# expansion.net
KiCad netlist of a schematic drawn in EAGLE
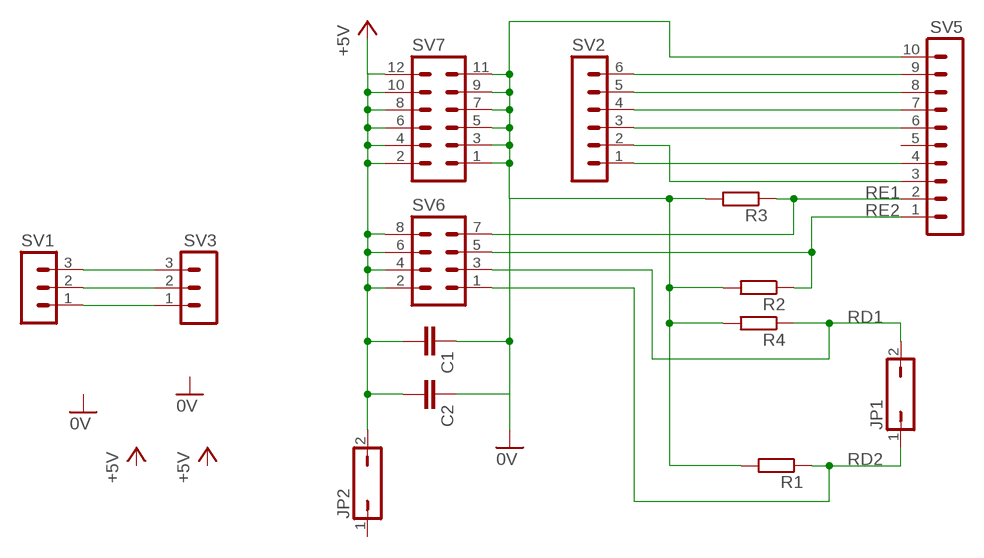
[diagram p0: schematic, sheet 1]

(export (version "E")
  (design (tool "Eeschema 10.0.6"))
  (components
    (comp (ref "C1")
      (value "C-EU025-030X050")
      (footprint "eagle-import:C025-030X050")
      (libsource (lib "eagle-import") (part "C-EU025-030X050"))
    )
    (comp (ref "C2")
      (value "C-EU025-030X050")
      (footprint "eagle-import:C025-030X050")
      (libsource (lib "eagle-import") (part "C-EU025-030X050"))
    )
    (comp (ref "JP1")
      (value "JP1Q")
      (footprint "eagle-import:JP1")
      (libsource (lib "eagle-import") (part "JP1Q"))
    )
    (comp (ref "JP2")
      (value "JP1Q")
      (footprint "eagle-import:JP1")
      (libsource (lib "eagle-import") (part "JP1Q"))
    )
    (comp (ref "R1")
      (value "R-EU_0207/10")
      (footprint "eagle-import:0207_10")
      (libsource (lib "eagle-import") (part "R-EU_0207/10"))
    )
    (comp (ref "R2")
      (value "R-EU_0207/5V")
      (footprint "eagle-import:0207_5V")
      (libsource (lib "eagle-import") (part "R-EU_0207/5V"))
    )
    (comp (ref "R3")
      (value "R-EU_0207/2V")
      (footprint "eagle-import:0207_2V")
      (libsource (lib "eagle-import") (part "R-EU_0207/2V"))
    )
    (comp (ref "R4")
      (value "R-EU_0204/7")
      (footprint "eagle-import:0204_7")
      (libsource (lib "eagle-import") (part "R-EU_0204/7"))
    )
    (comp (ref "SV1")
      (value "MA03-1")
      (footprint "eagle-import:MA03-1")
      (libsource (lib "eagle-import") (part "MA03-1"))
    )
    (comp (ref "SV2")
      (value "MA06-1")
      (footprint "eagle-import:MA06-1")
      (libsource (lib "eagle-import") (part "MA06-1"))
    )
    (comp (ref "SV3")
      (value "MA03-1")
      (footprint "eagle-import:MA03-1")
      (libsource (lib "eagle-import") (part "MA03-1"))
    )
    (comp (ref "SV5")
      (value "MA10-1")
      (footprint "eagle-import:MA10-1")
      (libsource (lib "eagle-import") (part "MA10-1"))
    )
    (comp (ref "SV6")
      (value "MA04-2")
      (footprint "eagle-import:MA04-2")
      (libsource (lib "eagle-import") (part "MA04-2"))
    )
    (comp (ref "SV7")
      (value "MA06-2")
      (footprint "eagle-import:MA06-2")
      (libsource (lib "eagle-import") (part "MA06-2"))
    )
  )
  (nets
    (net (code "1") (name "+5V") (class "Default")
      (node (ref "C1") (pin "2") (pinfunction "2_2") (pintype "passive"))
      (node (ref "C2") (pin "2") (pinfunction "2_2") (pintype "passive"))
      (node (ref "JP2") (pin "2") (pinfunction "2_2") (pintype "passive"))
      (node (ref "SV6") (pin "2") (pinfunction "2_2") (pintype "passive"))
      (node (ref "SV6") (pin "4") (pinfunction "4_4") (pintype "passive"))
      (node (ref "SV6") (pin "6") (pinfunction "6_6") (pintype "passive"))
      (node (ref "SV6") (pin "8") (pinfunction "8_8") (pintype "passive"))
      (node (ref "SV7") (pin "10") (pinfunction "10_10") (pintype "passive"))
      (node (ref "SV7") (pin "12") (pinfunction "12_12") (pintype "passive"))
      (node (ref "SV7") (pin "2") (pinfunction "2_2") (pintype "passive"))
      (node (ref "SV7") (pin "4") (pinfunction "4_4") (pintype "passive"))
      (node (ref "SV7") (pin "6") (pinfunction "6_6") (pintype "passive"))
      (node (ref "SV7") (pin "8") (pinfunction "8_8") (pintype "passive"))
    )
    (net (code "2") (name "/RD1") (class "Default")
      (node (ref "JP1") (pin "2") (pinfunction "2_2") (pintype "passive"))
      (node (ref "R4") (pin "1") (pinfunction "1_1") (pintype "passive"))
      (node (ref "SV6") (pin "3") (pinfunction "3_3") (pintype "passive"))
    )
    (net (code "3") (name "/RD2") (class "Default")
      (node (ref "JP1") (pin "1") (pinfunction "1_1") (pintype "passive"))
      (node (ref "R1") (pin "1") (pinfunction "1_1") (pintype "passive"))
      (node (ref "SV6") (pin "1") (pinfunction "1_1") (pintype "passive"))
    )
    (net (code "4") (name "/RE1") (class "Default")
      (node (ref "R3") (pin "1") (pinfunction "1_1") (pintype "passive"))
      (node (ref "SV5") (pin "2") (pinfunction "2_2") (pintype "passive"))
      (node (ref "SV6") (pin "7") (pinfunction "7_7") (pintype "passive"))
    )
    (net (code "5") (name "/RE2") (class "Default")
      (node (ref "R2") (pin "1") (pinfunction "1_1") (pintype "passive"))
      (node (ref "SV5") (pin "1") (pinfunction "1_1") (pintype "passive"))
      (node (ref "SV6") (pin "5") (pinfunction "5_5") (pintype "passive"))
    )
    (net (code "6") (name "0V") (class "Default")
      (node (ref "C1") (pin "1") (pinfunction "1_1") (pintype "passive"))
      (node (ref "C2") (pin "1") (pinfunction "1_1") (pintype "passive"))
      (node (ref "R1") (pin "2") (pinfunction "2_2") (pintype "passive"))
      (node (ref "R2") (pin "2") (pinfunction "2_2") (pintype "passive"))
      (node (ref "R3") (pin "2") (pinfunction "2_2") (pintype "passive"))
      (node (ref "R4") (pin "2") (pinfunction "2_2") (pintype "passive"))
      (node (ref "SV5") (pin "10") (pinfunction "10_10") (pintype "passive"))
      (node (ref "SV7") (pin "1") (pinfunction "1_1") (pintype "passive"))
      (node (ref "SV7") (pin "11") (pinfunction "11_11") (pintype "passive"))
      (node (ref "SV7") (pin "3") (pinfunction "3_3") (pintype "passive"))
      (node (ref "SV7") (pin "5") (pinfunction "5_5") (pintype "passive"))
      (node (ref "SV7") (pin "7") (pinfunction "7_7") (pintype "passive"))
      (node (ref "SV7") (pin "9") (pinfunction "9_9") (pintype "passive"))
    )
    (net (code "7") (name "Net-(SV1-Pad1)") (class "Default")
      (node (ref "SV1") (pin "1") (pinfunction "1_1") (pintype "passive"))
      (node (ref "SV3") (pin "1") (pinfunction "1_1") (pintype "passive"))
    )
    (net (code "8") (name "Net-(SV1-Pad2)") (class "Default")
      (node (ref "SV1") (pin "2") (pinfunction "2_2") (pintype "passive"))
      (node (ref "SV3") (pin "2") (pinfunction "2_2") (pintype "passive"))
    )
    (net (code "9") (name "Net-(SV1-Pad3)") (class "Default")
      (node (ref "SV1") (pin "3") (pinfunction "3_3") (pintype "passive"))
      (node (ref "SV3") (pin "3") (pinfunction "3_3") (pintype "passive"))
    )
    (net (code "10") (name "Net-(SV2-Pad1)") (class "Default")
      (node (ref "SV2") (pin "1") (pinfunction "1_1") (pintype "passive"))
      (node (ref "SV5") (pin "4") (pinfunction "4_4") (pintype "passive"))
    )
    (net (code "11") (name "Net-(SV2-Pad2)") (class "Default")
      (node (ref "SV2") (pin "2") (pinfunction "2_2") (pintype "passive"))
      (node (ref "SV5") (pin "3") (pinfunction "3_3") (pintype "passive"))
    )
    (net (code "12") (name "Net-(SV2-Pad3)") (class "Default")
      (node (ref "SV2") (pin "3") (pinfunction "3_3") (pintype "passive"))
      (node (ref "SV5") (pin "6") (pinfunction "6_6") (pintype "passive"))
    )
    (net (code "13") (name "Net-(SV2-Pad4)") (class "Default")
      (node (ref "SV2") (pin "4") (pinfunction "4_4") (pintype "passive"))
      (node (ref "SV5") (pin "7") (pinfunction "7_7") (pintype "passive"))
    )
    (net (code "14") (name "Net-(SV2-Pad5)") (class "Default")
      (node (ref "SV2") (pin "5") (pinfunction "5_5") (pintype "passive"))
      (node (ref "SV5") (pin "8") (pinfunction "8_8") (pintype "passive"))
    )
    (net (code "15") (name "Net-(SV2-Pad6)") (class "Default")
      (node (ref "SV2") (pin "6") (pinfunction "6_6") (pintype "passive"))
      (node (ref "SV5") (pin "9") (pinfunction "9_9") (pintype "passive"))
    )
    (net (code "16") (name "unconnected-(JP2-Pad1)") (class "Default")
      (node (ref "JP2") (pin "1") (pinfunction "1_1") (pintype "passive"))
    )
    (net (code "17") (name "unconnected-(SV5-Pad5)") (class "Default")
      (node (ref "SV5") (pin "5") (pinfunction "5_5") (pintype "passive"))
    )
  )
)
